# Driver_PaP.net
KiCad netlist of a schematic drawn in EAGLE
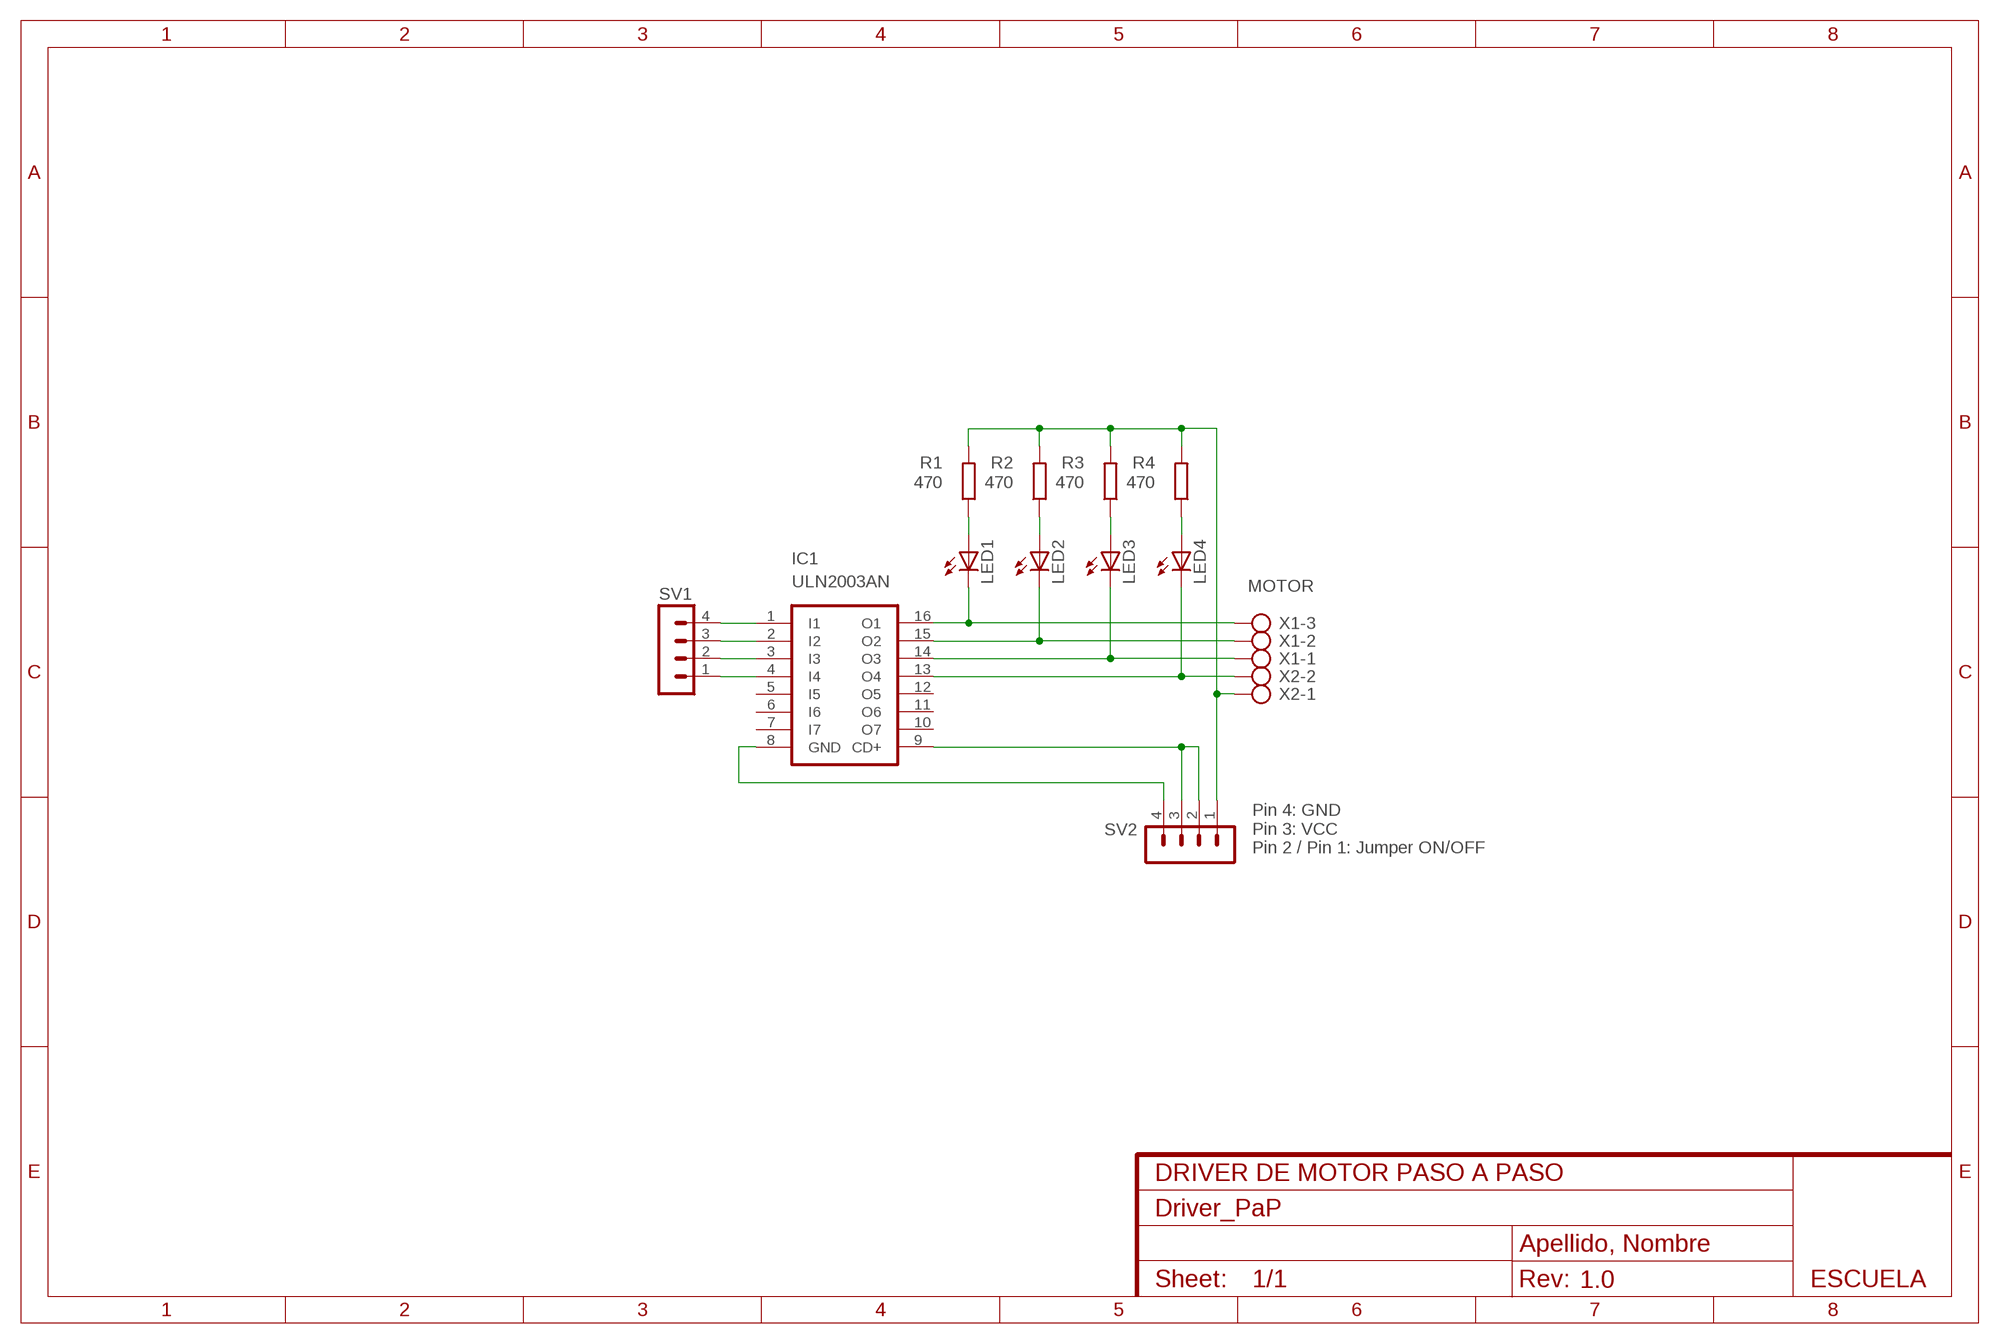
[diagram p0: schematic, sheet 1]

(export (version "E")
  (design (tool "Eeschema 10.0.6"))
  (components
    (comp (ref "IC1")
      (value "ULN2003AN")
      (footprint "eagle-import:DIL16")
      (libsource (lib "eagle-import") (part "ULN2003AN"))
    )
    (comp (ref "LED1")
      (value "LED3MM")
      (footprint "eagle-import:LED_3MM")
      (libsource (lib "eagle-import") (part "LED3MM"))
    )
    (comp (ref "LED2")
      (value "LED3MM")
      (footprint "eagle-import:LED_3MM")
      (libsource (lib "eagle-import") (part "LED3MM"))
    )
    (comp (ref "LED3")
      (value "LED3MM")
      (footprint "eagle-import:LED_3MM")
      (libsource (lib "eagle-import") (part "LED3MM"))
    )
    (comp (ref "LED4")
      (value "LED3MM")
      (footprint "eagle-import:LED_3MM")
      (libsource (lib "eagle-import") (part "LED3MM"))
    )
    (comp (ref "R1")
      (value "470")
      (footprint "eagle-import:0204_7")
      (libsource (lib "eagle-import") (part "RESISTOR-EU0204/7"))
    )
    (comp (ref "R2")
      (value "470")
      (footprint "eagle-import:0204_7")
      (libsource (lib "eagle-import") (part "RESISTOR-EU0204/7"))
    )
    (comp (ref "R3")
      (value "470")
      (footprint "eagle-import:0204_7")
      (libsource (lib "eagle-import") (part "RESISTOR-EU0204/7"))
    )
    (comp (ref "R4")
      (value "470")
      (footprint "eagle-import:0204_7")
      (libsource (lib "eagle-import") (part "RESISTOR-EU0204/7"))
    )
    (comp (ref "SV1")
      (value "MA04-1")
      (footprint "eagle-import:MA04-1")
      (libsource (lib "eagle-import") (part "MA04-1"))
    )
    (comp (ref "SV2")
      (value "PWR")
      (footprint "eagle-import:MA04-1")
      (libsource (lib "eagle-import") (part "MA04-1"))
    )
    (comp (ref "X1")
      (value "MOTOR")
      (footprint "eagle-import:AK500_3")
      (libsource (lib "eagle-import") (part "BORNERA_AK500/3"))
    )
    (comp (ref "X2")
      (value "BORNERA_AK500/2")
      (footprint "eagle-import:AK500_2")
      (libsource (lib "eagle-import") (part "BORNERA_AK500/2"))
    )
  )
  (nets
    (net (code "1") (name "Net-(IC1-CD+)") (class "Default")
      (node (ref "IC1") (pin "9") (pinfunction "CD+_9") (pintype "passive"))
      (node (ref "SV2") (pin "2") (pinfunction "2_2") (pintype "passive"))
      (node (ref "SV2") (pin "3") (pinfunction "3_3") (pintype "passive"))
    )
    (net (code "2") (name "Net-(IC1-GND)") (class "Default")
      (node (ref "IC1") (pin "8") (pinfunction "GND_8") (pintype "power_in"))
      (node (ref "SV2") (pin "4") (pinfunction "4_4") (pintype "passive"))
    )
    (net (code "3") (name "Net-(IC1-I1)") (class "Default")
      (node (ref "IC1") (pin "1") (pinfunction "I1_1") (pintype "input"))
      (node (ref "SV1") (pin "4") (pinfunction "4_4") (pintype "passive"))
    )
    (net (code "4") (name "Net-(IC1-I2)") (class "Default")
      (node (ref "IC1") (pin "2") (pinfunction "I2_2") (pintype "input"))
      (node (ref "SV1") (pin "3") (pinfunction "3_3") (pintype "passive"))
    )
    (net (code "5") (name "Net-(IC1-I3)") (class "Default")
      (node (ref "IC1") (pin "3") (pinfunction "I3_3") (pintype "input"))
      (node (ref "SV1") (pin "2") (pinfunction "2_2") (pintype "passive"))
    )
    (net (code "6") (name "Net-(IC1-I4)") (class "Default")
      (node (ref "IC1") (pin "4") (pinfunction "I4_4") (pintype "input"))
      (node (ref "SV1") (pin "1") (pinfunction "1_1") (pintype "passive"))
    )
    (net (code "7") (name "Net-(IC1-O1)") (class "Default")
      (node (ref "IC1") (pin "16") (pinfunction "O1_16") (pintype "open_collector"))
      (node (ref "LED1") (pin "K") (pinfunction "C_K") (pintype "passive"))
      (node (ref "X1") (pin "3") (pinfunction "KL_3") (pintype "passive"))
    )
    (net (code "8") (name "Net-(IC1-O2)") (class "Default")
      (node (ref "IC1") (pin "15") (pinfunction "O2_15") (pintype "open_collector"))
      (node (ref "LED2") (pin "K") (pinfunction "C_K") (pintype "passive"))
      (node (ref "X1") (pin "2") (pinfunction "KL_2") (pintype "passive"))
    )
    (net (code "9") (name "Net-(IC1-O3)") (class "Default")
      (node (ref "IC1") (pin "14") (pinfunction "O3_14") (pintype "open_collector"))
      (node (ref "LED3") (pin "K") (pinfunction "C_K") (pintype "passive"))
      (node (ref "X1") (pin "1") (pinfunction "KL_1") (pintype "passive"))
    )
    (net (code "10") (name "Net-(IC1-O4)") (class "Default")
      (node (ref "IC1") (pin "13") (pinfunction "O4_13") (pintype "open_collector"))
      (node (ref "LED4") (pin "K") (pinfunction "C_K") (pintype "passive"))
      (node (ref "X2") (pin "2") (pinfunction "KL_2") (pintype "passive"))
    )
    (net (code "11") (name "Net-(LED1-PadA)") (class "Default")
      (node (ref "LED1") (pin "A") (pinfunction "A_A") (pintype "passive"))
      (node (ref "R1") (pin "1") (pinfunction "1_1") (pintype "passive"))
    )
    (net (code "12") (name "Net-(LED2-PadA)") (class "Default")
      (node (ref "LED2") (pin "A") (pinfunction "A_A") (pintype "passive"))
      (node (ref "R2") (pin "1") (pinfunction "1_1") (pintype "passive"))
    )
    (net (code "13") (name "Net-(LED3-PadA)") (class "Default")
      (node (ref "LED3") (pin "A") (pinfunction "A_A") (pintype "passive"))
      (node (ref "R3") (pin "1") (pinfunction "1_1") (pintype "passive"))
    )
    (net (code "14") (name "Net-(LED4-PadA)") (class "Default")
      (node (ref "LED4") (pin "A") (pinfunction "A_A") (pintype "passive"))
      (node (ref "R4") (pin "1") (pinfunction "1_1") (pintype "passive"))
    )
    (net (code "15") (name "Net-(X2A-KL)") (class "Default")
      (node (ref "R1") (pin "2") (pinfunction "2_2") (pintype "passive"))
      (node (ref "R2") (pin "2") (pinfunction "2_2") (pintype "passive"))
      (node (ref "R3") (pin "2") (pinfunction "2_2") (pintype "passive"))
      (node (ref "R4") (pin "2") (pinfunction "2_2") (pintype "passive"))
      (node (ref "SV2") (pin "1") (pinfunction "1_1") (pintype "passive"))
      (node (ref "X2") (pin "1") (pinfunction "KL_1") (pintype "passive"))
    )
    (net (code "16") (name "unconnected-(IC1-I5-Pad5)") (class "Default")
      (node (ref "IC1") (pin "5") (pinfunction "I5_5") (pintype "input"))
    )
    (net (code "17") (name "unconnected-(IC1-I6-Pad6)") (class "Default")
      (node (ref "IC1") (pin "6") (pinfunction "I6_6") (pintype "input"))
    )
    (net (code "18") (name "unconnected-(IC1-I7-Pad7)") (class "Default")
      (node (ref "IC1") (pin "7") (pinfunction "I7_7") (pintype "input"))
    )
    (net (code "19") (name "unconnected-(IC1-O5-Pad12)") (class "Default")
      (node (ref "IC1") (pin "12") (pinfunction "O5_12") (pintype "open_collector"))
    )
    (net (code "20") (name "unconnected-(IC1-O6-Pad11)") (class "Default")
      (node (ref "IC1") (pin "11") (pinfunction "O6_11") (pintype "open_collector"))
    )
    (net (code "21") (name "unconnected-(IC1-O7-Pad10)") (class "Default")
      (node (ref "IC1") (pin "10") (pinfunction "O7_10") (pintype "open_collector"))
    )
  )
)
